# PCB.net
KiCad netlist of a schematic drawn in Altium Designer
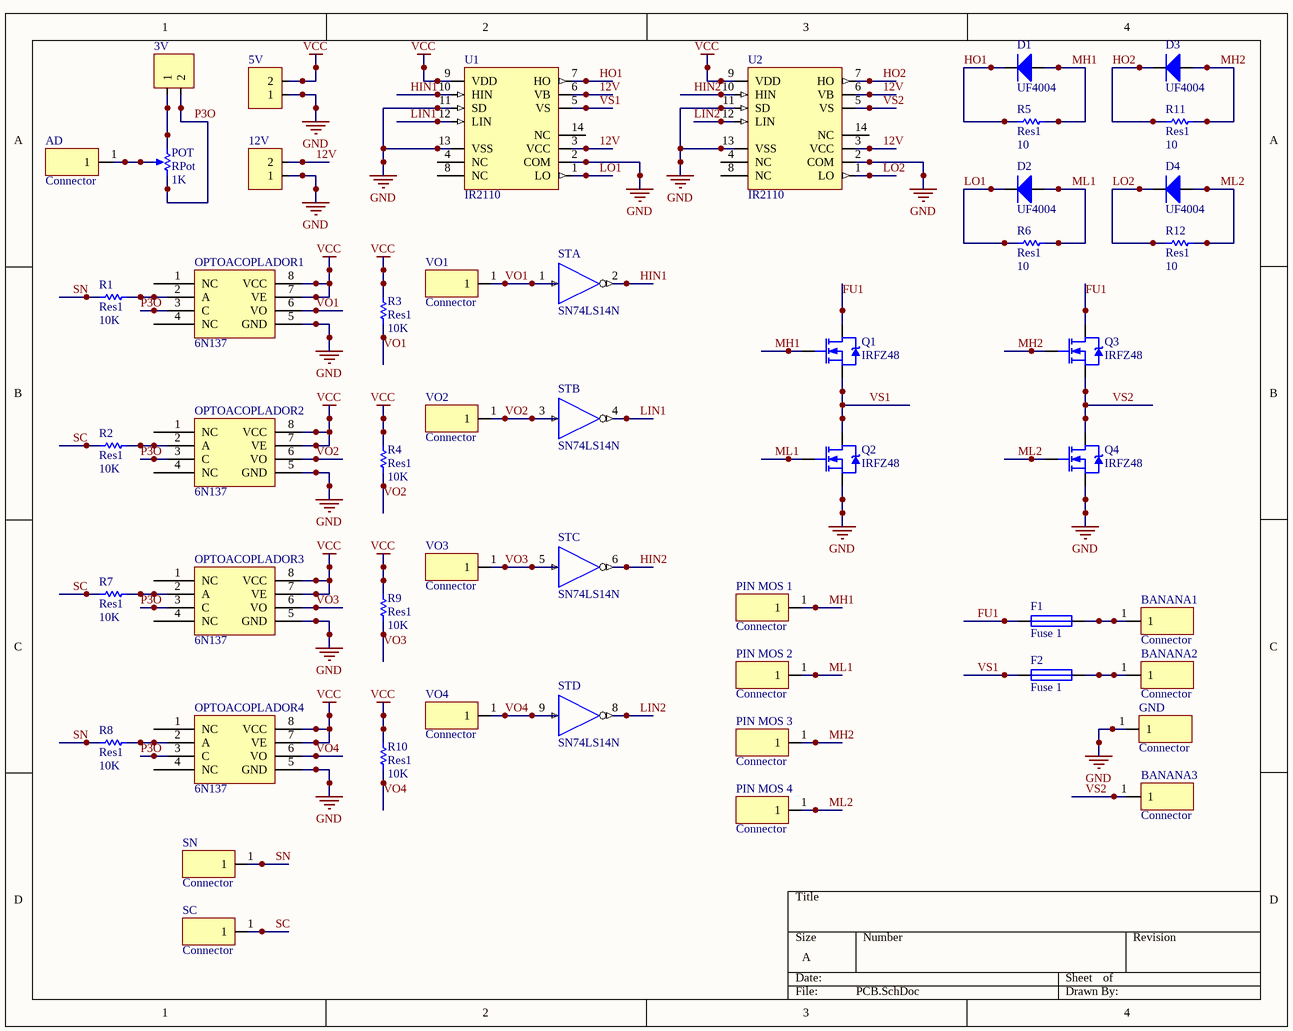
[diagram p0: PCB.SchDoc]

(export (version "E")
  (design (tool "Eeschema 10.0.6"))
  (components
    (comp (ref "3V")
      (value "WE-Terminal Blocks Screw Type 691214110002")
      (footprint "691214110002")
      (description "WR-TBL Terminal block - serie 2141 - 3.5mm")
      (fields
        (field (name "MANUFACTURER") "Würth Elektronik eiSos GmbH")
        (field (name "PARTNO") "691214110002")
        (field (name "CREATED DATE") "8 Novenber 2013")
        (field (name "CREATED BY") "Karrer Zheng")
      )
      (libsource (lib "") (part "WE-Terminal Blocks Screw Type 691214110002_1"))
    )
    (comp (ref "5V")
      (value "WE-Terminal Blocks Screw Type 691214110002")
      (footprint "691214110002")
      (description "WR-TBL Terminal block - serie 2141 - 3.5mm")
      (fields
        (field (name "MANUFACTURER") "Würth Elektronik eiSos GmbH")
        (field (name "PARTNO") "691214110002")
        (field (name "CREATED DATE") "8 Novenber 2013")
        (field (name "CREATED BY") "Karrer Zheng")
      )
      (libsource (lib "WE_WR-TBL_Rising Cage System_3.50 mm_rev15a") (part "WE-Terminal Blocks Screw Type 691214110002"))
    )
    (comp (ref "12V")
      (value "WE-Terminal Blocks Screw Type 691214110002")
      (footprint "691214110002")
      (description "WR-TBL Terminal block - serie 2141 - 3.5mm")
      (fields
        (field (name "MANUFACTURER") "Würth Elektronik eiSos GmbH")
        (field (name "PARTNO") "691214110002")
        (field (name "CREATED DATE") "8 Novenber 2013")
        (field (name "CREATED BY") "Karrer Zheng")
      )
      (libsource (lib "WE_WR-TBL_Rising Cage System_3.50 mm_rev15a") (part "WE-Terminal Blocks Screw Type 691214110002"))
    )
    (comp (ref "AD")
      (value "Connector")
      (footprint "1x1x2.54 Pin Header TH V")
      (libsource (lib "IFS_Altium") (part "Header 1x1"))
    )
    (comp (ref "BANANA1")
      (value "Connector")
      (footprint "1x1x2.54 Pin Header TH V")
      (libsource (lib "") (part "Header 1x1_1"))
    )
    (comp (ref "BANANA2")
      (value "Connector")
      (footprint "1x1x2.54 Pin Header TH V")
      (libsource (lib "") (part "Header 1x1_1"))
    )
    (comp (ref "BANANA3")
      (value "Connector")
      (footprint "1x1x2.54 Pin Header TH V")
      (libsource (lib "") (part "Header 1x1_1"))
    )
    (comp (ref "D1")
      (value "UF4004")
      (footprint "DO-35")
      (description "High Conductance Low Leakage Diode")
      (fields (field (name "PUBLISHER") "Altium Limited"))
      (libsource (lib "FSC Discrete Diode") (part "FDH333"))
    )
    (comp (ref "D2")
      (value "UF4004")
      (footprint "DO-35")
      (description "High Conductance Low Leakage Diode")
      (fields (field (name "PUBLISHER") "Altium Limited"))
      (libsource (lib "FSC Discrete Diode") (part "FDH333"))
    )
    (comp (ref "D3")
      (value "UF4004")
      (footprint "DO-35")
      (description "High Conductance Low Leakage Diode")
      (fields (field (name "PUBLISHER") "Altium Limited"))
      (libsource (lib "FSC Discrete Diode") (part "FDH333"))
    )
    (comp (ref "D4")
      (value "UF4004")
      (footprint "DO-35")
      (description "High Conductance Low Leakage Diode")
      (fields (field (name "PUBLISHER") "Altium Limited"))
      (libsource (lib "FSC Discrete Diode") (part "FDH333"))
    )
    (comp (ref "F1")
      (value "Fuse 1")
      (footprint "PIN-W2/E2.8")
      (description "Fuse")
      (fields (field (name "PUBLISHER") "Altium Limited"))
      (libsource (lib "Miscellaneous Devices") (part "Fuse 1"))
    )
    (comp (ref "F2")
      (value "Fuse 1")
      (footprint "PIN-W2/E2.8")
      (description "Fuse")
      (fields (field (name "PUBLISHER") "Altium Limited"))
      (libsource (lib "Miscellaneous Devices") (part "Fuse 1"))
    )
    (comp (ref "GND")
      (value "Connector")
      (footprint "1x1x2.54 Pin Header TH V")
      (libsource (lib "") (part "Header 1x1_1"))
    )
    (comp (ref "OPTOACOPLADOR1")
      (value "6N137")
      (footprint "*DIP762W50P254L977H451Q8")
      (description "High CMR, High Speed TTL Compatible Optocouplers")
      (fields
        (field (name "DIGI-KEY_PART_NUMBER") "751-1262-5-ND")
        (field (name "MF") "Everlight Electronics")
      )
      (libsource (lib "6N137") (part "6N137"))
    )
    (comp (ref "OPTOACOPLADOR2")
      (value "6N137")
      (footprint "*DIP762W50P254L977H451Q8")
      (description "High CMR, High Speed TTL Compatible Optocouplers")
      (fields
        (field (name "DIGI-KEY_PART_NUMBER") "751-1262-5-ND")
        (field (name "MF") "Everlight Electronics")
      )
      (libsource (lib "6N137") (part "6N137"))
    )
    (comp (ref "OPTOACOPLADOR3")
      (value "6N137")
      (footprint "*DIP762W50P254L977H451Q8")
      (description "High CMR, High Speed TTL Compatible Optocouplers")
      (fields
        (field (name "DIGI-KEY_PART_NUMBER") "751-1262-5-ND")
        (field (name "MF") "Everlight Electronics")
      )
      (libsource (lib "6N137") (part "6N137"))
    )
    (comp (ref "OPTOACOPLADOR4")
      (value "6N137")
      (footprint "*DIP762W50P254L977H451Q8")
      (description "High CMR, High Speed TTL Compatible Optocouplers")
      (fields
        (field (name "DIGI-KEY_PART_NUMBER") "751-1262-5-ND")
        (field (name "MF") "Everlight Electronics")
      )
      (libsource (lib "6N137") (part "6N137"))
    )
    (comp (ref "PIN MOS 1")
      (value "Connector")
      (footprint "1x1x2.54 Pin Header TH V")
      (libsource (lib "IFS_Altium") (part "Header 1x1"))
    )
    (comp (ref "PIN MOS 2")
      (value "Connector")
      (footprint "1x1x2.54 Pin Header TH V")
      (libsource (lib "IFS_Altium") (part "Header 1x1"))
    )
    (comp (ref "PIN MOS 3")
      (value "Connector")
      (footprint "1x1x2.54 Pin Header TH V")
      (libsource (lib "IFS_Altium") (part "Header 1x1"))
    )
    (comp (ref "PIN MOS 4")
      (value "Connector")
      (footprint "1x1x2.54 Pin Header TH V")
      (libsource (lib "IFS_Altium") (part "Header 1x1"))
    )
    (comp (ref "POT")
      (value "RPot")
      (footprint "VR5")
      (description "Potentiometer")
      (fields (field (name "ALTIUM_VALUE") "1K") (field (name "PUBLISHER") "Altium Limited"))
      (libsource (lib "Miscellaneous Devices") (part "RPot"))
    )
    (comp (ref "Q1")
      (value "IRFZ48")
      (footprint "TO-220AB")
      (description "HEXFET N-Channel Power MOSFET")
      (fields (field (name "PUBLISHER") "Altium Limited"))
      (libsource (lib "IR Discrete MOSFET - Power") (part "IRFZ48"))
    )
    (comp (ref "Q2")
      (value "IRFZ48")
      (footprint "TO-220AB")
      (description "HEXFET N-Channel Power MOSFET")
      (fields (field (name "PUBLISHER") "Altium Limited"))
      (libsource (lib "IR Discrete MOSFET - Power") (part "IRFZ48"))
    )
    (comp (ref "Q3")
      (value "IRFZ48")
      (footprint "TO-220AB")
      (description "HEXFET N-Channel Power MOSFET")
      (fields (field (name "PUBLISHER") "Altium Limited"))
      (libsource (lib "IR Discrete MOSFET - Power") (part "IRFZ48"))
    )
    (comp (ref "Q4")
      (value "IRFZ48")
      (footprint "TO-220AB")
      (description "HEXFET N-Channel Power MOSFET")
      (fields (field (name "PUBLISHER") "Altium Limited"))
      (libsource (lib "IR Discrete MOSFET - Power") (part "IRFZ48"))
    )
    (comp (ref "R1")
      (value "Res1")
      (footprint "AXIAL-0.3")
      (description "Resistor")
      (fields (field (name "ALTIUM_VALUE") "10K") (field (name "PUBLISHER") "Altium Limited"))
      (libsource (lib "Miscellaneous Devices") (part "Res1"))
    )
    (comp (ref "R2")
      (value "Res1")
      (footprint "AXIAL-0.3")
      (description "Resistor")
      (fields (field (name "ALTIUM_VALUE") "10K") (field (name "PUBLISHER") "Altium Limited"))
      (libsource (lib "Miscellaneous Devices") (part "Res1"))
    )
    (comp (ref "R3")
      (value "Res1")
      (footprint "AXIAL-0.3")
      (description "Resistor")
      (fields (field (name "ALTIUM_VALUE") "10K") (field (name "PUBLISHER") "Altium Limited"))
      (libsource (lib "Miscellaneous Devices") (part "Res1"))
    )
    (comp (ref "R4")
      (value "Res1")
      (footprint "AXIAL-0.3")
      (description "Resistor")
      (fields (field (name "ALTIUM_VALUE") "10K") (field (name "PUBLISHER") "Altium Limited"))
      (libsource (lib "Miscellaneous Devices") (part "Res1"))
    )
    (comp (ref "R5")
      (value "Res1")
      (footprint "AXIAL-0.3")
      (description "Resistor")
      (fields (field (name "ALTIUM_VALUE") "10") (field (name "PUBLISHER") "Altium Limited"))
      (libsource (lib "Miscellaneous Devices") (part "Res1"))
    )
    (comp (ref "R6")
      (value "Res1")
      (footprint "AXIAL-0.3")
      (description "Resistor")
      (fields (field (name "ALTIUM_VALUE") "10") (field (name "PUBLISHER") "Altium Limited"))
      (libsource (lib "Miscellaneous Devices") (part "Res1"))
    )
    (comp (ref "R7")
      (value "Res1")
      (footprint "AXIAL-0.3")
      (description "Resistor")
      (fields (field (name "ALTIUM_VALUE") "10K") (field (name "PUBLISHER") "Altium Limited"))
      (libsource (lib "Miscellaneous Devices") (part "Res1"))
    )
    (comp (ref "R8")
      (value "Res1")
      (footprint "AXIAL-0.3")
      (description "Resistor")
      (fields (field (name "ALTIUM_VALUE") "10K") (field (name "PUBLISHER") "Altium Limited"))
      (libsource (lib "Miscellaneous Devices") (part "Res1"))
    )
    (comp (ref "R9")
      (value "Res1")
      (footprint "AXIAL-0.3")
      (description "Resistor")
      (fields (field (name "ALTIUM_VALUE") "10K") (field (name "PUBLISHER") "Altium Limited"))
      (libsource (lib "Miscellaneous Devices") (part "Res1"))
    )
    (comp (ref "R10")
      (value "Res1")
      (footprint "AXIAL-0.3")
      (description "Resistor")
      (fields (field (name "ALTIUM_VALUE") "10K") (field (name "PUBLISHER") "Altium Limited"))
      (libsource (lib "Miscellaneous Devices") (part "Res1"))
    )
    (comp (ref "R11")
      (value "Res1")
      (footprint "AXIAL-0.3")
      (description "Resistor")
      (fields (field (name "ALTIUM_VALUE") "10") (field (name "PUBLISHER") "Altium Limited"))
      (libsource (lib "Miscellaneous Devices") (part "Res1"))
    )
    (comp (ref "R12")
      (value "Res1")
      (footprint "AXIAL-0.3")
      (description "Resistor")
      (fields (field (name "ALTIUM_VALUE") "10") (field (name "PUBLISHER") "Altium Limited"))
      (libsource (lib "Miscellaneous Devices") (part "Res1"))
    )
    (comp (ref "SC")
      (value "Connector")
      (footprint "1x1x2.54 Pin Header TH V")
      (libsource (lib "IFS_Altium") (part "Header 1x1"))
    )
    (comp (ref "SN")
      (value "Connector")
      (footprint "1x1x2.54 Pin Header TH V")
      (libsource (lib "IFS_Altium") (part "Header 1x1"))
    )
    (comp (ref "ST")
      (value "SN74LS14N")
      (footprint "N014")
      (description "Hex Schmitt-Trigger Inverter")
      (fields (field (name "PUBLISHER") "Altium Limited"))
      (libsource (lib "TI Logic Gate 2") (part "SN74LS14N"))
    )
    (comp (ref "U1")
      (value "IR2110")
      (footprint "PDIP14")
      (description "High and Low Side Driver")
      (fields (field (name "PUBLISHER") "Altium Limited"))
      (libsource (lib "IR Interface Bridge Driver") (part "IR2110"))
    )
    (comp (ref "U2")
      (value "IR2110")
      (footprint "PDIP14")
      (description "High and Low Side Driver")
      (fields (field (name "PUBLISHER") "Altium Limited"))
      (libsource (lib "IR Interface Bridge Driver") (part "IR2110"))
    )
    (comp (ref "VO1")
      (value "Connector")
      (footprint "1x1x2.54 Pin Header TH V")
      (libsource (lib "IFS_Altium") (part "Header 1x1"))
    )
    (comp (ref "VO2")
      (value "Connector")
      (footprint "1x1x2.54 Pin Header TH V")
      (libsource (lib "IFS_Altium") (part "Header 1x1"))
    )
    (comp (ref "VO3")
      (value "Connector")
      (footprint "1x1x2.54 Pin Header TH V")
      (libsource (lib "IFS_Altium") (part "Header 1x1"))
    )
    (comp (ref "VO4")
      (value "Connector")
      (footprint "1x1x2.54 Pin Header TH V")
      (libsource (lib "IFS_Altium") (part "Header 1x1"))
    )
  )
  (nets
    (net (code "1") (name "/12V") (class "Default")
      (node (ref "12V") (pin "2") (pinfunction "2_2") (pintype "passive"))
      (node (ref "U1") (pin "3") (pinfunction "VCC_3") (pintype "power_in"))
      (node (ref "U1") (pin "6") (pinfunction "VB_6") (pintype "power_in"))
      (node (ref "U2") (pin "3") (pinfunction "VCC_3") (pintype "power_in"))
      (node (ref "U2") (pin "6") (pinfunction "VB_6") (pintype "power_in"))
    )
    (net (code "2") (name "/FU1") (class "Default")
      (node (ref "F1") (pin "2") (pinfunction "2_2") (pintype "passive"))
      (node (ref "Q1") (pin "2") (pinfunction "D_2") (pintype "passive"))
      (node (ref "Q3") (pin "2") (pinfunction "D_2") (pintype "passive"))
    )
    (net (code "3") (name "/HIN1") (class "Default")
      (node (ref "ST") (pin "2") (pinfunction "Y_2") (pintype "output"))
      (node (ref "U1") (pin "10") (pinfunction "HIN_10") (pintype "input"))
    )
    (net (code "4") (name "/HIN2") (class "Default")
      (node (ref "ST") (pin "6") (pinfunction "Y_6") (pintype "output"))
      (node (ref "U2") (pin "10") (pinfunction "HIN_10") (pintype "input"))
    )
    (net (code "5") (name "/HO1") (class "Default")
      (node (ref "D1") (pin "2") (pinfunction "K_2") (pintype "passive"))
      (node (ref "R5") (pin "1") (pinfunction "1_1") (pintype "passive"))
      (node (ref "U1") (pin "7") (pinfunction "HO_7") (pintype "output"))
    )
    (net (code "6") (name "/HO2") (class "Default")
      (node (ref "D3") (pin "2") (pinfunction "K_2") (pintype "passive"))
      (node (ref "R11") (pin "1") (pinfunction "1_1") (pintype "passive"))
      (node (ref "U2") (pin "7") (pinfunction "HO_7") (pintype "output"))
    )
    (net (code "7") (name "/LIN1") (class "Default")
      (node (ref "ST") (pin "4") (pinfunction "Y_4") (pintype "output"))
      (node (ref "U1") (pin "12") (pinfunction "LIN_12") (pintype "input"))
    )
    (net (code "8") (name "/LIN2") (class "Default")
      (node (ref "ST") (pin "8") (pinfunction "Y_8") (pintype "output"))
      (node (ref "U2") (pin "12") (pinfunction "LIN_12") (pintype "input"))
    )
    (net (code "9") (name "/LO1") (class "Default")
      (node (ref "D2") (pin "2") (pinfunction "K_2") (pintype "passive"))
      (node (ref "R6") (pin "1") (pinfunction "1_1") (pintype "passive"))
      (node (ref "U1") (pin "1") (pinfunction "LO_1") (pintype "output"))
    )
    (net (code "10") (name "/LO2") (class "Default")
      (node (ref "D4") (pin "2") (pinfunction "K_2") (pintype "passive"))
      (node (ref "R12") (pin "1") (pinfunction "1_1") (pintype "passive"))
      (node (ref "U2") (pin "1") (pinfunction "LO_1") (pintype "output"))
    )
    (net (code "11") (name "/MH1") (class "Default")
      (node (ref "D1") (pin "1") (pinfunction "A_1") (pintype "passive"))
      (node (ref "PIN MOS 1") (pin "1") (pinfunction "1_1") (pintype "passive"))
      (node (ref "Q1") (pin "1") (pinfunction "G_1") (pintype "passive"))
      (node (ref "R5") (pin "2") (pinfunction "2_2") (pintype "passive"))
    )
    (net (code "12") (name "/MH2") (class "Default")
      (node (ref "D3") (pin "1") (pinfunction "A_1") (pintype "passive"))
      (node (ref "PIN MOS 3") (pin "1") (pinfunction "1_1") (pintype "passive"))
      (node (ref "Q3") (pin "1") (pinfunction "G_1") (pintype "passive"))
      (node (ref "R11") (pin "2") (pinfunction "2_2") (pintype "passive"))
    )
    (net (code "13") (name "/ML1") (class "Default")
      (node (ref "D2") (pin "1") (pinfunction "A_1") (pintype "passive"))
      (node (ref "PIN MOS 2") (pin "1") (pinfunction "1_1") (pintype "passive"))
      (node (ref "Q2") (pin "1") (pinfunction "G_1") (pintype "passive"))
      (node (ref "R6") (pin "2") (pinfunction "2_2") (pintype "passive"))
    )
    (net (code "14") (name "/ML2") (class "Default")
      (node (ref "D4") (pin "1") (pinfunction "A_1") (pintype "passive"))
      (node (ref "PIN MOS 4") (pin "1") (pinfunction "1_1") (pintype "passive"))
      (node (ref "Q4") (pin "1") (pinfunction "G_1") (pintype "passive"))
      (node (ref "R12") (pin "2") (pinfunction "2_2") (pintype "passive"))
    )
    (net (code "15") (name "/P3O") (class "Default")
      (node (ref "3V") (pin "2") (pinfunction "2_2") (pintype "passive"))
      (node (ref "OPTOACOPLADOR1") (pin "3") (pinfunction "C_3") (pintype "passive"))
      (node (ref "OPTOACOPLADOR2") (pin "3") (pinfunction "C_3") (pintype "passive"))
      (node (ref "OPTOACOPLADOR3") (pin "3") (pinfunction "C_3") (pintype "passive"))
      (node (ref "OPTOACOPLADOR4") (pin "3") (pinfunction "C_3") (pintype "passive"))
      (node (ref "POT") (pin "2") (pinfunction "BOT_2") (pintype "passive"))
    )
    (net (code "16") (name "/SC") (class "Default")
      (node (ref "R2") (pin "1") (pinfunction "1_1") (pintype "passive"))
      (node (ref "R7") (pin "1") (pinfunction "1_1") (pintype "passive"))
      (node (ref "SC") (pin "1") (pinfunction "1_1") (pintype "passive"))
    )
    (net (code "17") (name "/SN") (class "Default")
      (node (ref "R1") (pin "1") (pinfunction "1_1") (pintype "passive"))
      (node (ref "R8") (pin "1") (pinfunction "1_1") (pintype "passive"))
      (node (ref "SN") (pin "1") (pinfunction "1_1") (pintype "passive"))
    )
    (net (code "18") (name "/VO1") (class "Default")
      (node (ref "OPTOACOPLADOR1") (pin "6") (pinfunction "VO_6") (pintype "passive"))
      (node (ref "R3") (pin "1") (pinfunction "1_1") (pintype "passive"))
      (node (ref "ST") (pin "1") (pinfunction "A_1") (pintype "input"))
      (node (ref "VO1") (pin "1") (pinfunction "1_1") (pintype "passive"))
    )
    (net (code "19") (name "/VO2") (class "Default")
      (node (ref "OPTOACOPLADOR2") (pin "6") (pinfunction "VO_6") (pintype "passive"))
      (node (ref "R4") (pin "1") (pinfunction "1_1") (pintype "passive"))
      (node (ref "ST") (pin "3") (pinfunction "A_3") (pintype "input"))
      (node (ref "VO2") (pin "1") (pinfunction "1_1") (pintype "passive"))
    )
    (net (code "20") (name "/VO3") (class "Default")
      (node (ref "OPTOACOPLADOR3") (pin "6") (pinfunction "VO_6") (pintype "passive"))
      (node (ref "R9") (pin "1") (pinfunction "1_1") (pintype "passive"))
      (node (ref "ST") (pin "5") (pinfunction "A_5") (pintype "input"))
      (node (ref "VO3") (pin "1") (pinfunction "1_1") (pintype "passive"))
    )
    (net (code "21") (name "/VO4") (class "Default")
      (node (ref "OPTOACOPLADOR4") (pin "6") (pinfunction "VO_6") (pintype "passive"))
      (node (ref "R10") (pin "1") (pinfunction "1_1") (pintype "passive"))
      (node (ref "ST") (pin "9") (pinfunction "A_9") (pintype "input"))
      (node (ref "VO4") (pin "1") (pinfunction "1_1") (pintype "passive"))
    )
    (net (code "22") (name "/VS1") (class "Default")
      (node (ref "F2") (pin "1") (pinfunction "1_1") (pintype "passive"))
      (node (ref "Q1") (pin "3") (pinfunction "S_3") (pintype "passive"))
      (node (ref "Q2") (pin "2") (pinfunction "D_2") (pintype "passive"))
      (node (ref "U1") (pin "5") (pinfunction "VS_5") (pintype "power_in"))
    )
    (net (code "23") (name "/VS2") (class "Default")
      (node (ref "BANANA3") (pin "1") (pinfunction "1_1") (pintype "passive"))
      (node (ref "Q3") (pin "3") (pinfunction "S_3") (pintype "passive"))
      (node (ref "Q4") (pin "2") (pinfunction "D_2") (pintype "passive"))
      (node (ref "U2") (pin "5") (pinfunction "VS_5") (pintype "power_in"))
    )
    (net (code "24") (name "GND") (class "Default")
      (node (ref "12V") (pin "1") (pinfunction "1_1") (pintype "passive"))
      (node (ref "5V") (pin "1") (pinfunction "1_1") (pintype "passive"))
      (node (ref "GND") (pin "1") (pinfunction "1_1") (pintype "passive"))
      (node (ref "OPTOACOPLADOR1") (pin "5") (pinfunction "GND_5") (pintype "passive"))
      (node (ref "OPTOACOPLADOR2") (pin "5") (pinfunction "GND_5") (pintype "passive"))
      (node (ref "OPTOACOPLADOR3") (pin "5") (pinfunction "GND_5") (pintype "passive"))
      (node (ref "OPTOACOPLADOR4") (pin "5") (pinfunction "GND_5") (pintype "passive"))
      (node (ref "Q2") (pin "3") (pinfunction "S_3") (pintype "passive"))
      (node (ref "Q4") (pin "3") (pinfunction "S_3") (pintype "passive"))
      (node (ref "ST") (pin "7") (pinfunction "GND_7") (pintype "power_in"))
      (node (ref "U1") (pin "11") (pinfunction "SD_11") (pintype "input"))
      (node (ref "U1") (pin "13") (pinfunction "VSS_13") (pintype "power_in"))
      (node (ref "U1") (pin "2") (pinfunction "COM_2") (pintype "power_in"))
      (node (ref "U2") (pin "11") (pinfunction "SD_11") (pintype "input"))
      (node (ref "U2") (pin "13") (pinfunction "VSS_13") (pintype "power_in"))
      (node (ref "U2") (pin "2") (pinfunction "COM_2") (pintype "power_in"))
    )
    (net (code "25") (name "Net-(BANANA1-Pad1)") (class "Default")
      (node (ref "BANANA1") (pin "1") (pinfunction "1_1") (pintype "passive"))
      (node (ref "F1") (pin "1") (pinfunction "1_1") (pintype "passive"))
    )
    (net (code "26") (name "Net-(BANANA2-Pad1)") (class "Default")
      (node (ref "BANANA2") (pin "1") (pinfunction "1_1") (pintype "passive"))
      (node (ref "F2") (pin "2") (pinfunction "2_2") (pintype "passive"))
    )
    (net (code "27") (name "Net-(OPTOACOPLADOR1-A)") (class "Default")
      (node (ref "OPTOACOPLADOR1") (pin "2") (pinfunction "A_2") (pintype "passive"))
      (node (ref "R1") (pin "2") (pinfunction "2_2") (pintype "passive"))
    )
    (net (code "28") (name "Net-(OPTOACOPLADOR2-A)") (class "Default")
      (node (ref "OPTOACOPLADOR2") (pin "2") (pinfunction "A_2") (pintype "passive"))
      (node (ref "R2") (pin "2") (pinfunction "2_2") (pintype "passive"))
    )
    (net (code "29") (name "Net-(OPTOACOPLADOR3-A)") (class "Default")
      (node (ref "OPTOACOPLADOR3") (pin "2") (pinfunction "A_2") (pintype "passive"))
      (node (ref "R7") (pin "2") (pinfunction "2_2") (pintype "passive"))
    )
    (net (code "30") (name "Net-(OPTOACOPLADOR4-A)") (class "Default")
      (node (ref "OPTOACOPLADOR4") (pin "2") (pinfunction "A_2") (pintype "passive"))
      (node (ref "R8") (pin "2") (pinfunction "2_2") (pintype "passive"))
    )
    (net (code "31") (name "Net-(POT-TAP)") (class "Default")
      (node (ref "AD") (pin "1") (pinfunction "1_1") (pintype "passive"))
      (node (ref "POT") (pin "3") (pinfunction "TAP_3") (pintype "passive"))
    )
    (net (code "32") (name "Net-(POT-TOP)") (class "Default")
      (node (ref "3V") (pin "1") (pinfunction "1_1") (pintype "passive"))
      (node (ref "POT") (pin "1") (pinfunction "TOP_1") (pintype "passive"))
    )
    (net (code "33") (name "VCC") (class "Default")
      (node (ref "5V") (pin "2") (pinfunction "2_2") (pintype "passive"))
      (node (ref "OPTOACOPLADOR1") (pin "7") (pinfunction "VE_7") (pintype "passive"))
      (node (ref "OPTOACOPLADOR1") (pin "8") (pinfunction "VCC_8") (pintype "passive"))
      (node (ref "OPTOACOPLADOR2") (pin "7") (pinfunction "VE_7") (pintype "passive"))
      (node (ref "OPTOACOPLADOR2") (pin "8") (pinfunction "VCC_8") (pintype "passive"))
      (node (ref "OPTOACOPLADOR3") (pin "7") (pinfunction "VE_7") (pintype "passive"))
      (node (ref "OPTOACOPLADOR3") (pin "8") (pinfunction "VCC_8") (pintype "passive"))
      (node (ref "OPTOACOPLADOR4") (pin "7") (pinfunction "VE_7") (pintype "passive"))
      (node (ref "OPTOACOPLADOR4") (pin "8") (pinfunction "VCC_8") (pintype "passive"))
      (node (ref "R10") (pin "2") (pinfunction "2_2") (pintype "passive"))
      (node (ref "R3") (pin "2") (pinfunction "2_2") (pintype "passive"))
      (node (ref "R4") (pin "2") (pinfunction "2_2") (pintype "passive"))
      (node (ref "R9") (pin "2") (pinfunction "2_2") (pintype "passive"))
      (node (ref "ST") (pin "14") (pinfunction "VCC_14") (pintype "power_in"))
      (node (ref "U1") (pin "9") (pinfunction "VDD_9") (pintype "power_in"))
      (node (ref "U2") (pin "9") (pinfunction "VDD_9") (pintype "power_in"))
    )
    (net (code "34") (name "unconnected-(OPTOACOPLADOR1-NC-Pad1)") (class "Default")
      (node (ref "OPTOACOPLADOR1") (pin "1") (pinfunction "NC_1") (pintype "passive"))
    )
    (net (code "35") (name "unconnected-(OPTOACOPLADOR1-NC-Pad4)") (class "Default")
      (node (ref "OPTOACOPLADOR1") (pin "4") (pinfunction "NC_4") (pintype "passive"))
    )
    (net (code "36") (name "unconnected-(OPTOACOPLADOR2-NC-Pad1)") (class "Default")
      (node (ref "OPTOACOPLADOR2") (pin "1") (pinfunction "NC_1") (pintype "passive"))
    )
    (net (code "37") (name "unconnected-(OPTOACOPLADOR2-NC-Pad4)") (class "Default")
      (node (ref "OPTOACOPLADOR2") (pin "4") (pinfunction "NC_4") (pintype "passive"))
    )
    (net (code "38") (name "unconnected-(OPTOACOPLADOR3-NC-Pad1)") (class "Default")
      (node (ref "OPTOACOPLADOR3") (pin "1") (pinfunction "NC_1") (pintype "passive"))
    )
    (net (code "39") (name "unconnected-(OPTOACOPLADOR3-NC-Pad4)") (class "Default")
      (node (ref "OPTOACOPLADOR3") (pin "4") (pinfunction "NC_4") (pintype "passive"))
    )
    (net (code "40") (name "unconnected-(OPTOACOPLADOR4-NC-Pad1)") (class "Default")
      (node (ref "OPTOACOPLADOR4") (pin "1") (pinfunction "NC_1") (pintype "passive"))
    )
    (net (code "41") (name "unconnected-(OPTOACOPLADOR4-NC-Pad4)") (class "Default")
      (node (ref "OPTOACOPLADOR4") (pin "4") (pinfunction "NC_4") (pintype "passive"))
    )
    (net (code "42") (name "unconnected-(U1-NC-Pad4)") (class "Default")
      (node (ref "U1") (pin "4") (pinfunction "NC_4") (pintype "passive"))
    )
    (net (code "43") (name "unconnected-(U1-NC-Pad8)") (class "Default")
      (node (ref "U1") (pin "8") (pinfunction "NC_8") (pintype "passive"))
    )
    (net (code "44") (name "unconnected-(U1-NC-Pad14)") (class "Default")
      (node (ref "U1") (pin "14") (pinfunction "NC_14") (pintype "passive"))
    )
    (net (code "45") (name "unconnected-(U2-NC-Pad4)") (class "Default")
      (node (ref "U2") (pin "4") (pinfunction "NC_4") (pintype "passive"))
    )
    (net (code "46") (name "unconnected-(U2-NC-Pad8)") (class "Default")
      (node (ref "U2") (pin "8") (pinfunction "NC_8") (pintype "passive"))
    )
    (net (code "47") (name "unconnected-(U2-NC-Pad14)") (class "Default")
      (node (ref "U2") (pin "14") (pinfunction "NC_14") (pintype "passive"))
    )
  )
)
